# digital-in.net
KiCad netlist of a schematic drawn in Altium Designer
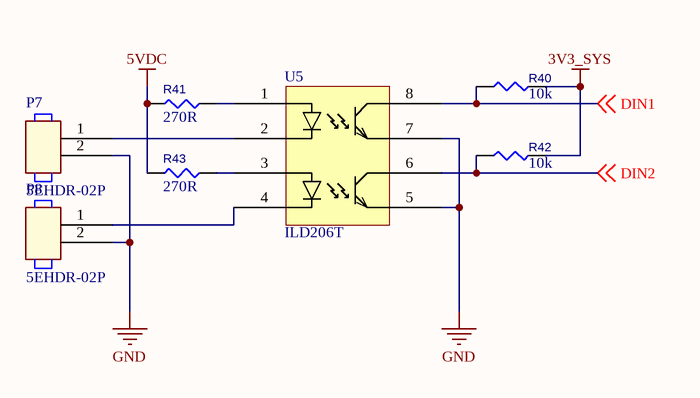
[diagram p0: digital-in.SchDoc]

(export (version "E")
  (design (tool "Eeschema 10.0.6"))
  (components
    (comp (ref "P7")
      (value "TE_282814-2")
      (footprint "TE_282814-2")
      (description "Terminal Block Connectors")
      (fields (field (name "MANUFACTURER") "TE Connectivity") (field (name "P/N") "5EHDR-02P"))
      (libsource (lib "spider") (part "TE_282814-2"))
    )
    (comp (ref "P8")
      (value "TE_282814-2")
      (footprint "TE_282814-2")
      (description "Terminal Block Connectors")
      (fields (field (name "MANUFACTURER") "TE Connectivity") (field (name "P/N") "5EHDR-02P"))
      (libsource (lib "spider") (part "TE_282814-2"))
    )
    (comp (ref "R40")
      (value "10k")
      (footprint "RESC1608X55N")
      (description "R0603")
      (libsource (lib "spider") (part "R0603"))
    )
    (comp (ref "R41")
      (value "270R")
      (footprint "RESC1608X55N")
      (description "R0603")
      (libsource (lib "spider") (part "R0603"))
    )
    (comp (ref "R42")
      (value "10k")
      (footprint "RESC1608X55N")
      (description "R0603")
      (libsource (lib "spider") (part "R0603"))
    )
    (comp (ref "R43")
      (value "270R")
      (footprint "RESC1608X55N")
      (description "R0603")
      (libsource (lib "spider") (part "R0603"))
    )
    (comp (ref "U5")
      (value "ILD206T")
      (footprint "SOIC-8-OPTOCOUPLER")
      (description "Optocoupler, Phototransistor Output, Dual Channel")
      (fields (field (name "P/N") "ILD206T"))
      (libsource (lib "spider") (part "ILD206T"))
    )
  )
  (nets
    (net (code "1") (name "3V3_SYS") (class "Default")
      (node (ref "R40") (pin "2") (pinfunction "2_2") (pintype "passive"))
      (node (ref "R42") (pin "2") (pinfunction "2_2") (pintype "passive"))
    )
    (net (code "2") (name "5VDC") (class "Default")
      (node (ref "R41") (pin "1") (pinfunction "1_1") (pintype "passive"))
      (node (ref "R43") (pin "1") (pinfunction "1_1") (pintype "passive"))
    )
    (net (code "3") (name "DIN1") (class "Default")
      (node (ref "R40") (pin "1") (pinfunction "1_1") (pintype "passive"))
      (node (ref "U5") (pin "8") (pinfunction "TC1_8") (pintype "passive"))
    )
    (net (code "4") (name "DIN2") (class "Default")
      (node (ref "R42") (pin "1") (pinfunction "1_1") (pintype "passive"))
      (node (ref "U5") (pin "6") (pinfunction "TC2_6") (pintype "passive"))
    )
    (net (code "5") (name "GND") (class "Default")
      (node (ref "P7") (pin "2") (pinfunction "2_2") (pintype "passive"))
      (node (ref "P8") (pin "2") (pinfunction "2_2") (pintype "passive"))
      (node (ref "U5") (pin "5") (pinfunction "TE1_5") (pintype "passive"))
      (node (ref "U5") (pin "7") (pinfunction "TE1_7") (pintype "passive"))
    )
    (net (code "6") (name "Net-(U5-A1)") (class "Default")
      (node (ref "R41") (pin "2") (pinfunction "2_2") (pintype "passive"))
      (node (ref "U5") (pin "1") (pinfunction "A1_1") (pintype "passive"))
    )
    (net (code "7") (name "Net-(U5-A2)") (class "Default")
      (node (ref "R43") (pin "2") (pinfunction "2_2") (pintype "passive"))
      (node (ref "U5") (pin "3") (pinfunction "A2_3") (pintype "passive"))
    )
    (net (code "8") (name "Net-(U5-C1)") (class "Default")
      (node (ref "P7") (pin "1") (pinfunction "1_1") (pintype "passive"))
      (node (ref "U5") (pin "2") (pinfunction "C1_2") (pintype "passive"))
    )
    (net (code "9") (name "Net-(U5-C2)") (class "Default")
      (node (ref "P8") (pin "1") (pinfunction "1_1") (pintype "passive"))
      (node (ref "U5") (pin "4") (pinfunction "C2_4") (pintype "passive"))
    )
  )
)
